# Sheet4.net
KiCad netlist of a schematic drawn in Altium Designer
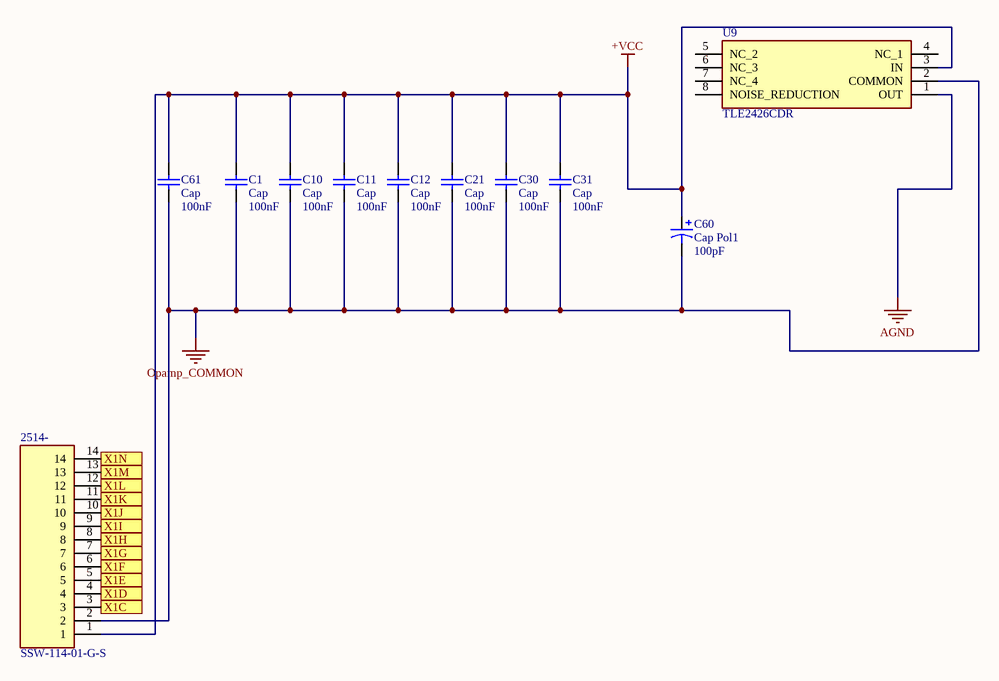
[diagram p0: Sheet4.SchDoc]

(export (version "E")
  (design (tool "Eeschema 10.0.6"))
  (components
    (comp (ref "2514-")
      (value "SSW-114-01-G-S")
      (footprint "PcbLib1:SHDR14W79P0X254_1X14_3607X241X851P")
      (description "Capacitor")
      (libsource (lib "*") (part "SSW-114-01-G-S"))
    )
    (comp (ref "C1")
      (value "Cap")
      (footprint "SMD_CAPACITOR")
      (description "Capacitor")
      (fields (field (name "ALTIUM_VALUE") "100nF") (field (name "PUBLISHER") "Altium Limited"))
      (libsource (lib "Miscellaneous Devices") (part "Cap"))
    )
    (comp (ref "C10")
      (value "Cap")
      (footprint "SMD_CAPACITOR")
      (description "Capacitor")
      (fields (field (name "ALTIUM_VALUE") "100nF") (field (name "PUBLISHER") "Altium Limited"))
      (libsource (lib "Miscellaneous Devices") (part "Cap"))
    )
    (comp (ref "C11")
      (value "Cap")
      (footprint "SMD_CAPACITOR")
      (description "Capacitor")
      (fields (field (name "ALTIUM_VALUE") "100nF") (field (name "PUBLISHER") "Altium Limited"))
      (libsource (lib "Miscellaneous Devices") (part "Cap"))
    )
    (comp (ref "C12")
      (value "Cap")
      (footprint "SMD_CAPACITOR")
      (description "Capacitor")
      (fields (field (name "ALTIUM_VALUE") "100nF") (field (name "PUBLISHER") "Altium Limited"))
      (libsource (lib "Miscellaneous Devices") (part "Cap"))
    )
    (comp (ref "C21")
      (value "Cap")
      (footprint "SMD_CAPACITOR")
      (description "Capacitor")
      (fields (field (name "ALTIUM_VALUE") "100nF") (field (name "PUBLISHER") "Altium Limited"))
      (libsource (lib "Miscellaneous Devices") (part "Cap"))
    )
    (comp (ref "C30")
      (value "Cap")
      (footprint "SMD_CAPACITOR")
      (description "Capacitor")
      (fields (field (name "ALTIUM_VALUE") "100nF") (field (name "PUBLISHER") "Altium Limited"))
      (libsource (lib "Miscellaneous Devices") (part "Cap"))
    )
    (comp (ref "C31")
      (value "Cap")
      (footprint "SMD_CAPACITOR")
      (description "Capacitor")
      (fields (field (name "ALTIUM_VALUE") "100nF") (field (name "PUBLISHER") "Altium Limited"))
      (libsource (lib "Miscellaneous Devices") (part "Cap"))
    )
    (comp (ref "C60")
      (value "Cap Pol1")
      (footprint "SMD_POLAR_CAPACITOR")
      (description "Polarized Capacitor (Radial)")
      (fields (field (name "ALTIUM_VALUE") "100pF") (field (name "PUBLISHER") "Altium Limited"))
      (libsource (lib "Miscellaneous Devices") (part "Cap Pol1"))
    )
    (comp (ref "C61")
      (value "Cap")
      (footprint "SMD_CAPACITOR")
      (description "Capacitor")
      (fields (field (name "ALTIUM_VALUE") "100nF") (field (name "PUBLISHER") "Altium Limited"))
      (libsource (lib "Miscellaneous Devices") (part "Cap"))
    )
    (comp (ref "U9")
      (value "TLE2426CDR")
      (footprint "PcbLib1:SOIC127P600X175-8N")
      (description "Integrated Circuit")
      (fields (field (name "MOUSER2 PART NUMBER") "595-TLE2426CDR"))
      (libsource (lib "equalizer_project") (part "TLE2426CDR"))
    )
  )
  (nets
    (net (code "1") (name "+VCC") (class "Default")
      (node (ref "2514-") (pin "1") (pinfunction "1_1") (pintype "passive"))
      (node (ref "C1") (pin "2") (pinfunction "2_2") (pintype "passive"))
      (node (ref "C10") (pin "2") (pinfunction "2_2") (pintype "passive"))
      (node (ref "C11") (pin "2") (pinfunction "2_2") (pintype "passive"))
      (node (ref "C12") (pin "2") (pinfunction "2_2") (pintype "passive"))
      (node (ref "C21") (pin "2") (pinfunction "2_2") (pintype "passive"))
      (node (ref "C30") (pin "2") (pinfunction "2_2") (pintype "passive"))
      (node (ref "C31") (pin "2") (pinfunction "2_2") (pintype "passive"))
      (node (ref "C60") (pin "1") (pinfunction "1_1") (pintype "passive"))
      (node (ref "C61") (pin "2") (pinfunction "2_2") (pintype "passive"))
      (node (ref "U9") (pin "3") (pinfunction "IN_3") (pintype "passive"))
    )
    (net (code "2") (name "/X1C") (class "Default")
      (node (ref "2514-") (pin "3") (pinfunction "3_3") (pintype "passive"))
    )
    (net (code "3") (name "/X1D") (class "Default")
      (node (ref "2514-") (pin "4") (pinfunction "4_4") (pintype "passive"))
    )
    (net (code "4") (name "/X1E") (class "Default")
      (node (ref "2514-") (pin "5") (pinfunction "5_5") (pintype "passive"))
    )
    (net (code "5") (name "/X1F") (class "Default")
      (node (ref "2514-") (pin "6") (pinfunction "6_6") (pintype "passive"))
    )
    (net (code "6") (name "/X1G") (class "Default")
      (node (ref "2514-") (pin "7") (pinfunction "7_7") (pintype "passive"))
    )
    (net (code "7") (name "/X1H") (class "Default")
      (node (ref "2514-") (pin "8") (pinfunction "8_8") (pintype "passive"))
    )
    (net (code "8") (name "/X1I") (class "Default")
      (node (ref "2514-") (pin "9") (pinfunction "9_9") (pintype "passive"))
    )
    (net (code "9") (name "/X1J") (class "Default")
      (node (ref "2514-") (pin "10") (pinfunction "10_10") (pintype "passive"))
    )
    (net (code "10") (name "/X1K") (class "Default")
      (node (ref "2514-") (pin "11") (pinfunction "11_11") (pintype "passive"))
    )
    (net (code "11") (name "/X1L") (class "Default")
      (node (ref "2514-") (pin "12") (pinfunction "12_12") (pintype "passive"))
    )
    (net (code "12") (name "/X1M") (class "Default")
      (node (ref "2514-") (pin "13") (pinfunction "13_13") (pintype "passive"))
    )
    (net (code "13") (name "/X1N") (class "Default")
      (node (ref "2514-") (pin "14") (pinfunction "14_14") (pintype "passive"))
    )
    (net (code "14") (name "AGND") (class "Default")
      (node (ref "U9") (pin "1") (pinfunction "OUT_1") (pintype "passive"))
    )
    (net (code "15") (name "Opamp_COMMON") (class "Default")
      (node (ref "2514-") (pin "2") (pinfunction "2_2") (pintype "passive"))
      (node (ref "C1") (pin "1") (pinfunction "1_1") (pintype "passive"))
      (node (ref "C10") (pin "1") (pinfunction "1_1") (pintype "passive"))
      (node (ref "C11") (pin "1") (pinfunction "1_1") (pintype "passive"))
      (node (ref "C12") (pin "1") (pinfunction "1_1") (pintype "passive"))
      (node (ref "C21") (pin "1") (pinfunction "1_1") (pintype "passive"))
      (node (ref "C30") (pin "1") (pinfunction "1_1") (pintype "passive"))
      (node (ref "C31") (pin "1") (pinfunction "1_1") (pintype "passive"))
      (node (ref "C60") (pin "2") (pinfunction "2_2") (pintype "passive"))
      (node (ref "C61") (pin "1") (pinfunction "1_1") (pintype "passive"))
      (node (ref "U9") (pin "2") (pinfunction "COMMON_2") (pintype "passive"))
    )
    (net (code "16") (name "unconnected-(U9-NC_1-Pad4)") (class "Default")
      (node (ref "U9") (pin "4") (pinfunction "NC_1_4") (pintype "passive"))
    )
    (net (code "17") (name "unconnected-(U9-NC_2-Pad5)") (class "Default")
      (node (ref "U9") (pin "5") (pinfunction "NC_2_5") (pintype "passive"))
    )
    (net (code "18") (name "unconnected-(U9-NC_3-Pad6)") (class "Default")
      (node (ref "U9") (pin "6") (pinfunction "NC_3_6") (pintype "passive"))
    )
    (net (code "19") (name "unconnected-(U9-NC_4-Pad7)") (class "Default")
      (node (ref "U9") (pin "7") (pinfunction "NC_4_7") (pintype "passive"))
    )
    (net (code "20") (name "unconnected-(U9-NOISE_REDUCTION-Pad8)") (class "Default")
      (node (ref "U9") (pin "8") (pinfunction "NOISE_REDUCTION_8") (pintype "passive"))
    )
  )
)
